# watchPogoSerial.net
KiCad netlist of a schematic drawn in EAGLE
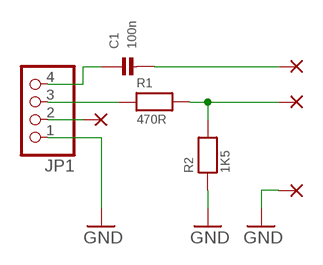
[diagram p0: schematic, sheet 1]

(export (version "E")
  (design (tool "Eeschema 10.0.6"))
  (components
    (comp (ref "C1")
      (value "100n")
      (footprint "eagle-import:0805")
      (libsource (lib "eagle-import") (part "CAP_CERAMIC0805"))
    )
    (comp (ref "JP1")
      (value "PINHD-1X4")
      (footprint "eagle-import:1X04")
      (libsource (lib "eagle-import") (part "PINHD-1X4"))
    )
    (comp (ref "PAD1")
      (value "PAD0.7-LONG")
      (footprint "eagle-import:PAD-0.75-LONG")
      (libsource (lib "eagle-import") (part "PAD0.7-LONG"))
    )
    (comp (ref "PAD3")
      (value "PAD0.7-LONG")
      (footprint "eagle-import:PAD-0.75-LONG")
      (libsource (lib "eagle-import") (part "PAD0.7-LONG"))
    )
    (comp (ref "PAD6")
      (value "PAD0.7-LONG")
      (footprint "eagle-import:PAD-0.75-LONG")
      (libsource (lib "eagle-import") (part "PAD0.7-LONG"))
    )
    (comp (ref "PAD12")
      (value "PAD0.7-LONG")
      (footprint "eagle-import:PAD-0.75-LONG")
      (libsource (lib "eagle-import") (part "PAD0.7-LONG"))
    )
    (comp (ref "R1")
      (value "470R")
      (footprint "eagle-import:0805")
      (libsource (lib "eagle-import") (part "RESISTOR0805"))
    )
    (comp (ref "R2")
      (value "1K5")
      (footprint "eagle-import:0805")
      (libsource (lib "eagle-import") (part "RESISTOR0805"))
    )
  )
  (nets
    (net (code "1") (name "GND") (class "Default")
      (node (ref "JP1") (pin "1") (pinfunction "1_1") (pintype "passive"))
      (node (ref "PAD1") (pin "P$1") (pinfunction "P$1_P$1") (pintype "passive"))
      (node (ref "R2") (pin "1") (pinfunction "1_1") (pintype "passive"))
    )
    (net (code "2") (name "Net-(C1-P$1)") (class "Default")
      (node (ref "C1") (pin "1") (pinfunction "P$1_1") (pintype "passive"))
      (node (ref "JP1") (pin "4") (pinfunction "4_4") (pintype "passive"))
    )
    (net (code "3") (name "Net-(C1-P$2)") (class "Default")
      (node (ref "C1") (pin "2") (pinfunction "P$2_2") (pintype "passive"))
      (node (ref "PAD3") (pin "P$1") (pinfunction "P$1_P$1") (pintype "passive"))
    )
    (net (code "4") (name "Net-(JP1-Pad2)") (class "Default")
      (node (ref "JP1") (pin "2") (pinfunction "2_2") (pintype "passive"))
      (node (ref "PAD12") (pin "P$1") (pinfunction "P$1_P$1") (pintype "passive"))
    )
    (net (code "5") (name "Net-(JP1-Pad3)") (class "Default")
      (node (ref "JP1") (pin "3") (pinfunction "3_3") (pintype "passive"))
      (node (ref "R1") (pin "1") (pinfunction "1_1") (pintype "passive"))
    )
    (net (code "6") (name "Net-(PAD6-PadP$1)") (class "Default")
      (node (ref "PAD6") (pin "P$1") (pinfunction "P$1_P$1") (pintype "passive"))
      (node (ref "R1") (pin "2") (pinfunction "2_2") (pintype "passive"))
      (node (ref "R2") (pin "2") (pinfunction "2_2") (pintype "passive"))
    )
  )
)
